# 140715_AriloTX_REV3_0_0_433MHZ_td.net
KiCad netlist of a schematic drawn in EAGLE
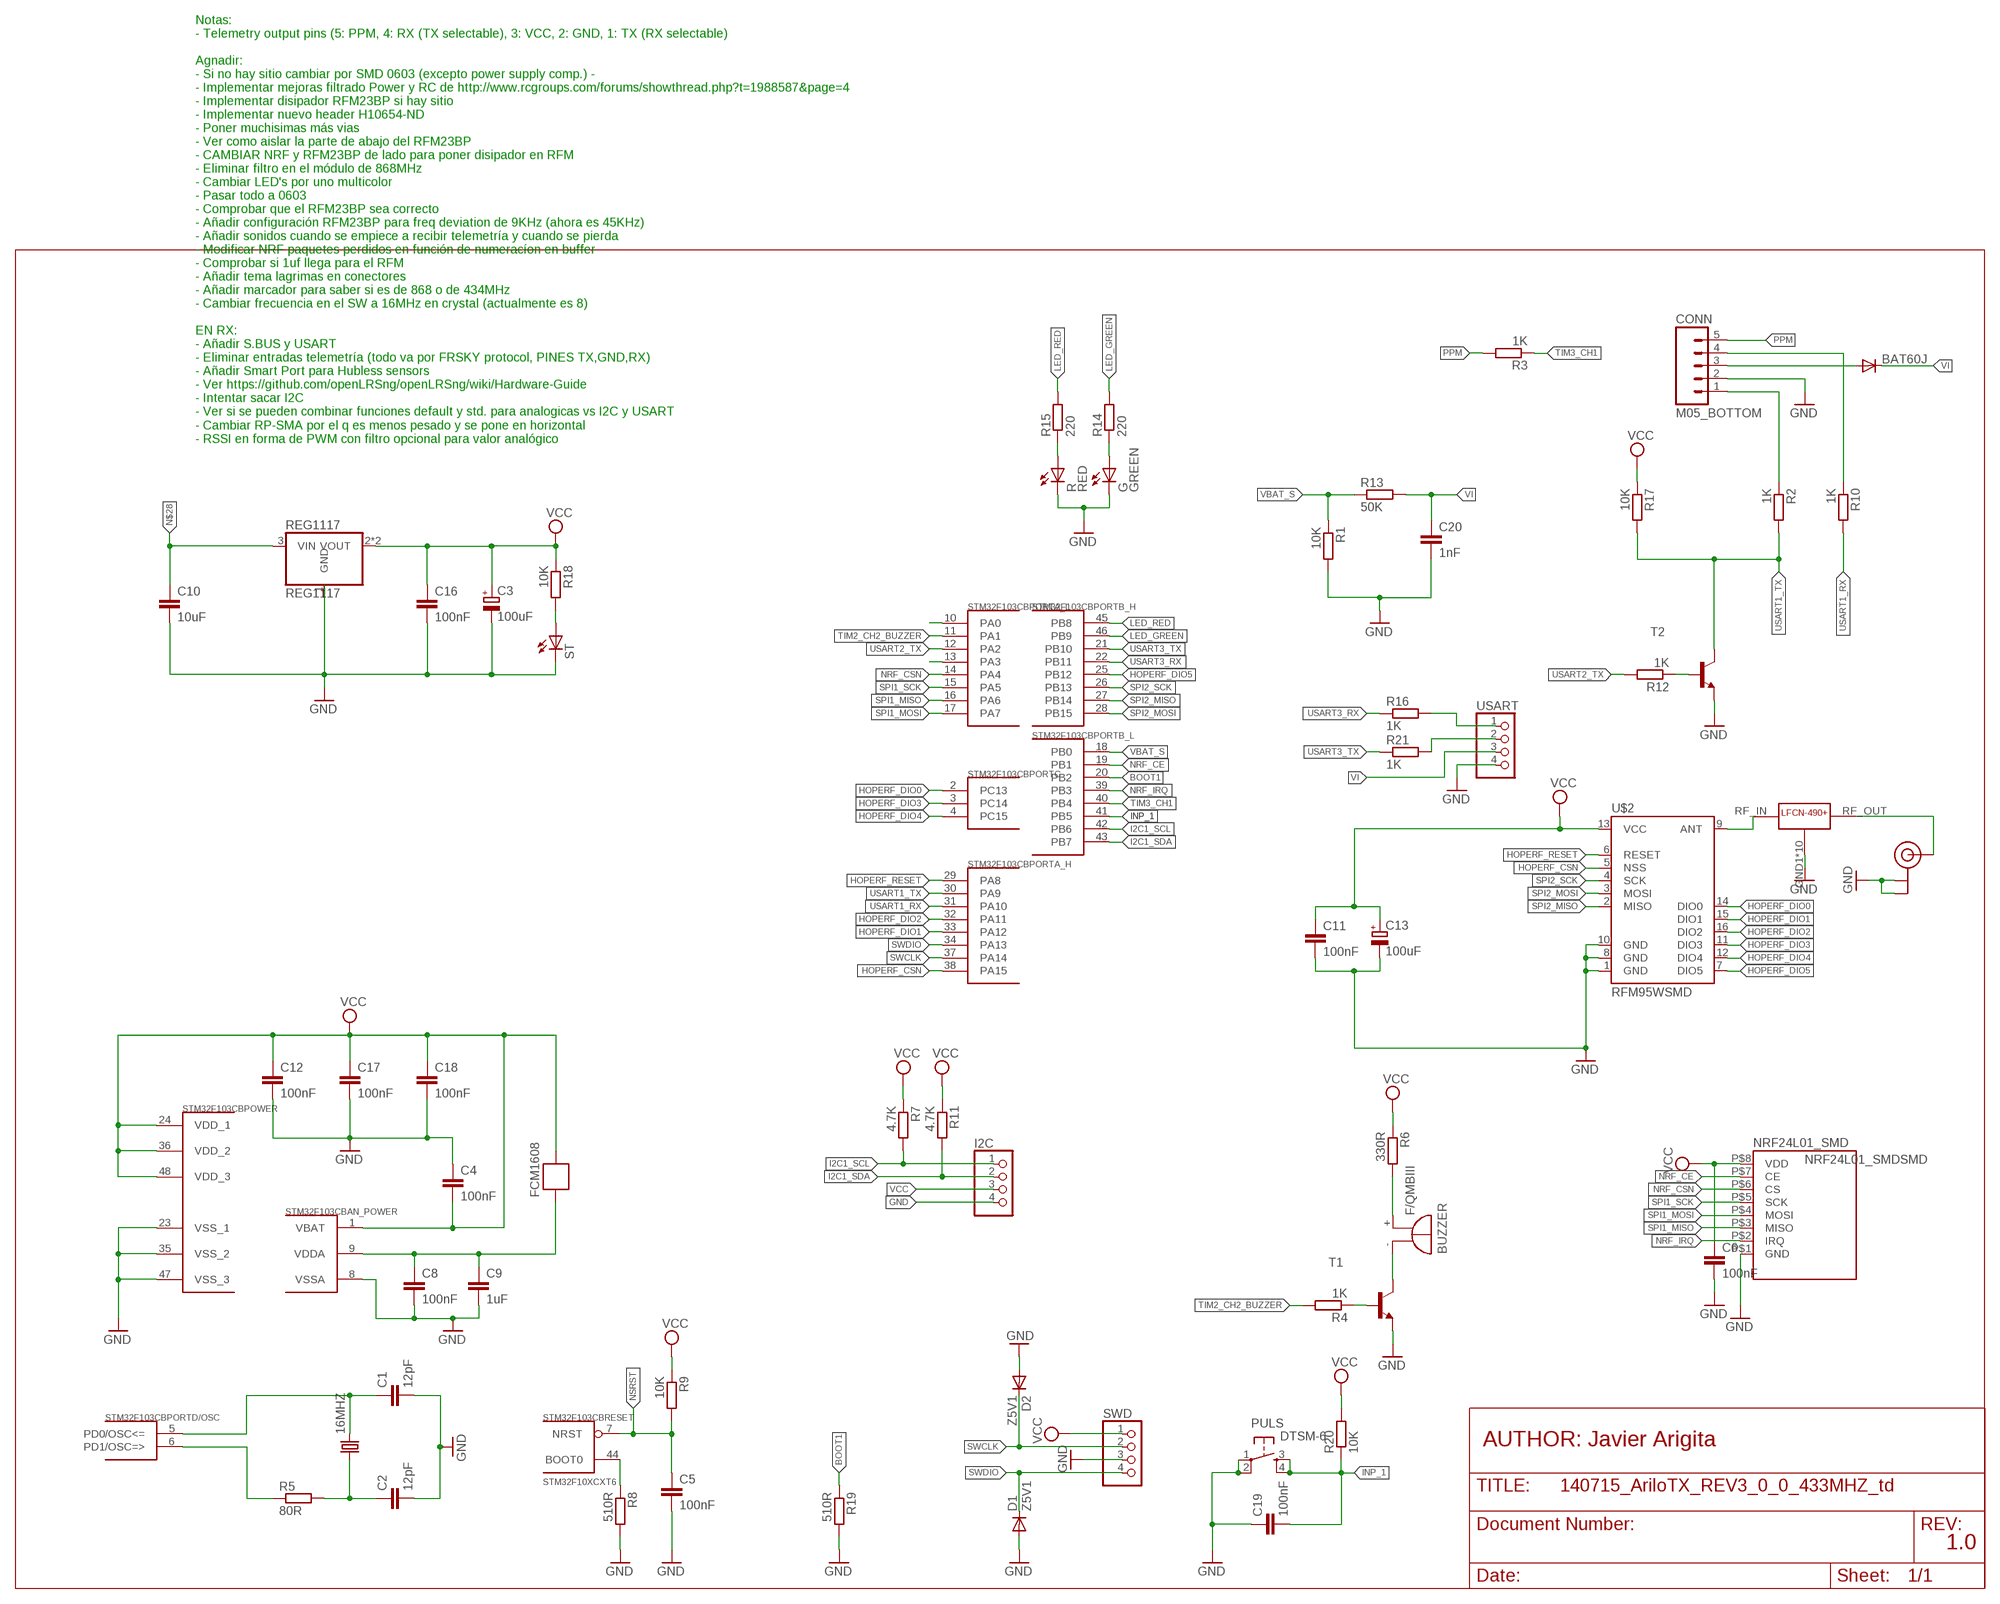
[diagram p0: schematic, sheet 1]

(export (version "E")
  (design (tool "Eeschema 10.0.6"))
  (components
    (comp (ref "16MHZ")
      (value "CRYSTAL5X3")
      (footprint "eagle-import:CRYSTAL-SMD-5X3")
      (libsource (lib "eagle-import") (part "CRYSTAL5X3"))
    )
    (comp (ref "BAT60J")
      (value "DIODE-SOD323-R")
      (footprint "eagle-import:SOD323-R")
      (libsource (lib "eagle-import") (part "DIODE-SOD323-R"))
    )
    (comp (ref "BUZZER")
      (value "F/QMBIII")
      (footprint "eagle-import:F_QMBIII")
      (libsource (lib "eagle-import") (part "F/QMBIII"))
    )
    (comp (ref "C1")
      (value "12pF")
      (footprint "eagle-import:C0603")
      (libsource (lib "eagle-import") (part "C-EUC0603"))
    )
    (comp (ref "C2")
      (value "12pF")
      (footprint "eagle-import:C0603")
      (libsource (lib "eagle-import") (part "C-EUC0603"))
    )
    (comp (ref "C3")
      (value "100uF")
      (footprint "eagle-import:SMC_B")
      (libsource (lib "eagle-import") (part "CPOL-EUSMCB"))
    )
    (comp (ref "C4")
      (value "100nF")
      (footprint "eagle-import:C0603")
      (libsource (lib "eagle-import") (part "C-EUC0603"))
    )
    (comp (ref "C5")
      (value "100nF")
      (footprint "eagle-import:C0603")
      (libsource (lib "eagle-import") (part "C-EUC0603"))
    )
    (comp (ref "C6")
      (value "100nF")
      (footprint "eagle-import:C0603")
      (libsource (lib "eagle-import") (part "C-EUC0603"))
    )
    (comp (ref "C8")
      (value "100nF")
      (footprint "eagle-import:C0603")
      (libsource (lib "eagle-import") (part "C-EUC0603"))
    )
    (comp (ref "C9")
      (value "1uF")
      (footprint "eagle-import:C0603")
      (libsource (lib "eagle-import") (part "C-EUC0603"))
    )
    (comp (ref "C10")
      (value "10uF")
      (footprint "eagle-import:C3216")
      (libsource (lib "eagle-import") (part "resistor_C-EUC3216"))
    )
    (comp (ref "C11")
      (value "100nF")
      (footprint "eagle-import:C0603")
      (libsource (lib "eagle-import") (part "C-EUC0603"))
    )
    (comp (ref "C12")
      (value "100nF")
      (footprint "eagle-import:C0603")
      (libsource (lib "eagle-import") (part "C-EUC0603"))
    )
    (comp (ref "C13")
      (value "100uF")
      (footprint "eagle-import:SMC_B")
      (libsource (lib "eagle-import") (part "CPOL-EUSMCB"))
    )
    (comp (ref "C16")
      (value "100nF")
      (footprint "eagle-import:C0603")
      (libsource (lib "eagle-import") (part "C-EUC0603"))
    )
    (comp (ref "C17")
      (value "100nF")
      (footprint "eagle-import:C0603")
      (libsource (lib "eagle-import") (part "C-EUC0603"))
    )
    (comp (ref "C18")
      (value "100nF")
      (footprint "eagle-import:C0603")
      (libsource (lib "eagle-import") (part "C-EUC0603"))
    )
    (comp (ref "C19")
      (value "100nF")
      (footprint "eagle-import:C0603")
      (libsource (lib "eagle-import") (part "C-EUC0603"))
    )
    (comp (ref "C20")
      (value "1nF")
      (footprint "eagle-import:C0603")
      (libsource (lib "eagle-import") (part "C-EUC0603"))
    )
    (comp (ref "CONN")
      (value "M05_BOTTOM")
      (footprint "eagle-import:M05_BOTTOM")
      (libsource (lib "eagle-import") (part "M05_BOTTOM"))
    )
    (comp (ref "D1")
      (value "Z5V1")
      (footprint "eagle-import:SOD323-R")
      (libsource (lib "eagle-import") (part "DIODE-SOD323-R"))
    )
    (comp (ref "D2")
      (value "Z5V1")
      (footprint "eagle-import:SOD323-R")
      (libsource (lib "eagle-import") (part "DIODE-SOD323-R"))
    )
    (comp (ref "FCM1608")
      (value "FERRITE-BEAD")
      (footprint "eagle-import:R0603")
      (libsource (lib "eagle-import") (part "FERRITE-BEAD"))
    )
    (comp (ref "G")
      (value "GREEN")
      (footprint "eagle-import:CHIP-LED0603")
      (libsource (lib "eagle-import") (part "LEDCHIP-LED0603"))
    )
    (comp (ref "I2C")
      (value "PINHD-1X4")
      (footprint "eagle-import:1X04")
      (libsource (lib "eagle-import") (part "PINHD-1X4"))
    )
    (comp (ref "LFCN490+")
      (value "LFCN490+")
      (footprint "eagle-import:LFCN490+")
      (libsource (lib "eagle-import") (part "LFCN490+"))
    )
    (comp (ref "NRF24L01_SMD")
      (value "NRF24L01_SMDSMD")
      (footprint "eagle-import:NRF24L01_SMD")
      (libsource (lib "eagle-import") (part "NRF24L01_SMDSMD"))
    )
    (comp (ref "PULS")
      (value "DTSM-6")
      (footprint "eagle-import:DTSM-6")
      (libsource (lib "eagle-import") (part "DTSM-6"))
    )
    (comp (ref "R")
      (value "RED")
      (footprint "eagle-import:CHIP-LED0603")
      (libsource (lib "eagle-import") (part "LEDCHIP-LED0603"))
    )
    (comp (ref "R1")
      (value "10K")
      (footprint "eagle-import:R0603")
      (libsource (lib "eagle-import") (part "R-EU_R0603"))
    )
    (comp (ref "R2")
      (value "1K")
      (footprint "eagle-import:R0603")
      (libsource (lib "eagle-import") (part "R-EU_R0603"))
    )
    (comp (ref "R3")
      (value "1K")
      (footprint "eagle-import:R0603")
      (libsource (lib "eagle-import") (part "R-EU_R0603"))
    )
    (comp (ref "R4")
      (value "1K")
      (footprint "eagle-import:R0603")
      (libsource (lib "eagle-import") (part "R-EU_R0603"))
    )
    (comp (ref "R5")
      (value "80R")
      (footprint "eagle-import:R0603")
      (libsource (lib "eagle-import") (part "R-EU_R0603"))
    )
    (comp (ref "R6")
      (value "330R")
      (footprint "eagle-import:R0603")
      (libsource (lib "eagle-import") (part "R-EU_R0603"))
    )
    (comp (ref "R7")
      (value "4.7K")
      (footprint "eagle-import:R0603")
      (libsource (lib "eagle-import") (part "R-EU_R0603"))
    )
    (comp (ref "R8")
      (value "510R")
      (footprint "eagle-import:R0603")
      (libsource (lib "eagle-import") (part "R-EU_R0603"))
    )
    (comp (ref "R9")
      (value "10K")
      (footprint "eagle-import:R0603")
      (libsource (lib "eagle-import") (part "R-EU_R0603"))
    )
    (comp (ref "R10")
      (value "1K")
      (footprint "eagle-import:R0603")
      (libsource (lib "eagle-import") (part "R-EU_R0603"))
    )
    (comp (ref "R11")
      (value "4.7K")
      (footprint "eagle-import:R0603")
      (libsource (lib "eagle-import") (part "R-EU_R0603"))
    )
    (comp (ref "R12")
      (value "1K")
      (footprint "eagle-import:R0603")
      (libsource (lib "eagle-import") (part "R-EU_R0603"))
    )
    (comp (ref "R13")
      (value "50K")
      (footprint "eagle-import:R0603")
      (libsource (lib "eagle-import") (part "R-EU_R0603"))
    )
    (comp (ref "R14")
      (value "220")
      (footprint "eagle-import:R0603")
      (libsource (lib "eagle-import") (part "R-EU_R0603"))
    )
    (comp (ref "R15")
      (value "220")
      (footprint "eagle-import:R0603")
      (libsource (lib "eagle-import") (part "R-EU_R0603"))
    )
    (comp (ref "R16")
      (value "1K")
      (footprint "eagle-import:R0603")
      (libsource (lib "eagle-import") (part "R-EU_R0603"))
    )
    (comp (ref "R17")
      (value "10K")
      (footprint "eagle-import:R0603")
      (libsource (lib "eagle-import") (part "R-EU_R0603"))
    )
    (comp (ref "R18")
      (value "10K")
      (footprint "eagle-import:R0603")
      (libsource (lib "eagle-import") (part "R-EU_R0603"))
    )
    (comp (ref "R19")
      (value "510R")
      (footprint "eagle-import:R0603")
      (libsource (lib "eagle-import") (part "R-EU_R0603"))
    )
    (comp (ref "R20")
      (value "10K")
      (footprint "eagle-import:R0603")
      (libsource (lib "eagle-import") (part "R-EU_R0603"))
    )
    (comp (ref "R21")
      (value "1K")
      (footprint "eagle-import:R0603")
      (libsource (lib "eagle-import") (part "R-EU_R0603"))
    )
    (comp (ref "REG1117")
      (value "REG1117")
      (footprint "eagle-import:SOT223")
      (libsource (lib "eagle-import") (part "REG1117"))
    )
    (comp (ref "ST")
      (value "LEDCHIP-LED0603")
      (footprint "eagle-import:CHIP-LED0603")
      (libsource (lib "eagle-import") (part "LEDCHIP-LED0603"))
    )
    (comp (ref "STM32F103CB")
      (value "STM32F10XCXT6")
      (footprint "eagle-import:TQFP48")
      (libsource (lib "eagle-import") (part "STM32F10XCXT6"))
    )
    (comp (ref "SWD")
      (value "PINHD-1X4")
      (footprint "eagle-import:1X04")
      (libsource (lib "eagle-import") (part "PINHD-1X4"))
    )
    (comp (ref "T1")
      (value "BC848-NPN-SOT23-BEC")
      (footprint "eagle-import:SOT23-BEC")
      (libsource (lib "eagle-import") (part "-NPN-SOT23-BECBC848"))
    )
    (comp (ref "T2")
      (value "BC848-NPN-SOT23-BEC")
      (footprint "eagle-import:SOT23-BEC")
      (libsource (lib "eagle-import") (part "-NPN-SOT23-BECBC848"))
    )
    (comp (ref "U$2")
      (value "RFM95WSMD")
      (footprint "eagle-import:MISIEK_RFM95W_SMD")
      (libsource (lib "eagle-import") (part "MISIEK_RFM95WSMD"))
    )
    (comp (ref "U.FL")
      (value "U.FL")
      (footprint "eagle-import:U.FL")
      (libsource (lib "eagle-import") (part "U.FL"))
    )
    (comp (ref "USART")
      (value "PINHD-1X4")
      (footprint "eagle-import:1X04")
      (libsource (lib "eagle-import") (part "PINHD-1X4"))
    )
  )
  (nets
    (net (code "1") (name "BOOT1") (class "Default")
      (node (ref "R19") (pin "1") (pinfunction "1_1") (pintype "passive"))
      (node (ref "STM32F103CB") (pin "20") (pinfunction "PB2_20") (pintype "bidirectional"))
    )
    (net (code "2") (name "GND") (class "Default")
      (node (ref "C1") (pin "2") (pinfunction "2_2") (pintype "passive"))
      (node (ref "C10") (pin "2") (pinfunction "2_2") (pintype "passive"))
      (node (ref "C11") (pin "2") (pinfunction "2_2") (pintype "passive"))
      (node (ref "C12") (pin "2") (pinfunction "2_2") (pintype "passive"))
      (node (ref "C13") (pin "-") (pinfunction "-_-") (pintype "passive"))
      (node (ref "C16") (pin "2") (pinfunction "2_2") (pintype "passive"))
      (node (ref "C17") (pin "2") (pinfunction "2_2") (pintype "passive"))
      (node (ref "C18") (pin "2") (pinfunction "2_2") (pintype "passive"))
      (node (ref "C19") (pin "1") (pinfunction "1_1") (pintype "passive"))
      (node (ref "C2") (pin "2") (pinfunction "2_2") (pintype "passive"))
      (node (ref "C20") (pin "2") (pinfunction "2_2") (pintype "passive"))
      (node (ref "C3") (pin "-") (pinfunction "-_-") (pintype "passive"))
      (node (ref "C4") (pin "1") (pinfunction "1_1") (pintype "passive"))
      (node (ref "C5") (pin "2") (pinfunction "2_2") (pintype "passive"))
      (node (ref "C6") (pin "2") (pinfunction "2_2") (pintype "passive"))
      (node (ref "C8") (pin "2") (pinfunction "2_2") (pintype "passive"))
      (node (ref "C9") (pin "2") (pinfunction "2_2") (pintype "passive"))
      (node (ref "CONN") (pin "2") (pinfunction "2_2") (pintype "passive"))
      (node (ref "D1") (pin "A") (pinfunction "A_A") (pintype "passive"))
      (node (ref "D2") (pin "A") (pinfunction "A_A") (pintype "passive"))
      (node (ref "G") (pin "C") (pinfunction "C_C") (pintype "passive"))
      (node (ref "I2C") (pin "4") (pinfunction "4_4") (pintype "passive"))
      (node (ref "LFCN490+") (pin "GND1") (pinfunction "GND_GND1") (pintype "bidirectional"))
      (node (ref "LFCN490+") (pin "GND10") (pinfunction "GND_GND10") (pintype "bidirectional"))
      (node (ref "LFCN490+") (pin "GND2") (pinfunction "GND_GND2") (pintype "bidirectional"))
      (node (ref "LFCN490+") (pin "GND3") (pinfunction "GND_GND3") (pintype "bidirectional"))
      (node (ref "LFCN490+") (pin "GND4") (pinfunction "GND_GND4") (pintype "bidirectional"))
      (node (ref "LFCN490+") (pin "GND5") (pinfunction "GND_GND5") (pintype "bidirectional"))
      (node (ref "LFCN490+") (pin "GND6") (pinfunction "GND_GND6") (pintype "bidirectional"))
      (node (ref "LFCN490+") (pin "GND7") (pinfunction "GND_GND7") (pintype "bidirectional"))
      (node (ref "LFCN490+") (pin "GND8") (pinfunction "GND_GND8") (pintype "bidirectional"))
      (node (ref "LFCN490+") (pin "GND9") (pinfunction "GND_GND9") (pintype "bidirectional"))
      (node (ref "NRF24L01_SMD") (pin "P$1") (pinfunction "GND_P$1") (pintype "power_in"))
      (node (ref "PULS") (pin "1") (pinfunction "1_1") (pintype "passive"))
      (node (ref "PULS") (pin "2") (pinfunction "2_2") (pintype "passive"))
      (node (ref "R") (pin "C") (pinfunction "C_C") (pintype "passive"))
      (node (ref "R1") (pin "2") (pinfunction "2_2") (pintype "passive"))
      (node (ref "R19") (pin "2") (pinfunction "2_2") (pintype "passive"))
      (node (ref "R8") (pin "2") (pinfunction "2_2") (pintype "passive"))
      (node (ref "REG1117") (pin "1") (pinfunction "GND_1") (pintype "power_in"))
      (node (ref "ST") (pin "C") (pinfunction "C_C") (pintype "passive"))
      (node (ref "STM32F103CB") (pin "23") (pinfunction "VSS_1_23") (pintype "power_in"))
      (node (ref "STM32F103CB") (pin "35") (pinfunction "VSS_2_35") (pintype "power_in"))
      (node (ref "STM32F103CB") (pin "47") (pinfunction "VSS_3_47") (pintype "power_in"))
      (node (ref "STM32F103CB") (pin "8") (pinfunction "VSSA_8") (pintype "power_in"))
      (node (ref "SWD") (pin "3") (pinfunction "3_3") (pintype "passive"))
      (node (ref "T1") (pin "E") (pinfunction "E_E") (pintype "passive"))
      (node (ref "T2") (pin "E") (pinfunction "E_E") (pintype "passive"))
      (node (ref "U$2") (pin "1") (pinfunction "GND_1") (pintype "power_in"))
      (node (ref "U$2") (pin "10") (pinfunction "GND_10") (pintype "power_in"))
      (node (ref "U$2") (pin "8") (pinfunction "GND_8") (pintype "power_in"))
      (node (ref "U.FL") (pin "P$1") (pinfunction "GND_P$1") (pintype "bidirectional"))
      (node (ref "U.FL") (pin "P$2") (pinfunction "GND_P$2") (pintype "bidirectional"))
      (node (ref "USART") (pin "4") (pinfunction "4_4") (pintype "passive"))
    )
    (net (code "3") (name "HOPERF_CSN") (class "Default")
      (node (ref "STM32F103CB") (pin "38") (pinfunction "PA15_38") (pintype "bidirectional"))
      (node (ref "U$2") (pin "5") (pinfunction "NSS_5") (pintype "input"))
    )
    (net (code "4") (name "HOPERF_DIO0") (class "Default")
      (node (ref "STM32F103CB") (pin "2") (pinfunction "PC13_2") (pintype "bidirectional"))
      (node (ref "U$2") (pin "14") (pinfunction "DIO0_14") (pintype "input"))
    )
    (net (code "5") (name "HOPERF_DIO1") (class "Default")
      (node (ref "STM32F103CB") (pin "33") (pinfunction "PA12_33") (pintype "bidirectional"))
      (node (ref "U$2") (pin "15") (pinfunction "DIO1_15") (pintype "input"))
    )
    (net (code "6") (name "HOPERF_DIO2") (class "Default")
      (node (ref "STM32F103CB") (pin "32") (pinfunction "PA11_32") (pintype "bidirectional"))
      (node (ref "U$2") (pin "16") (pinfunction "DIO2_16") (pintype "input"))
    )
    (net (code "7") (name "HOPERF_DIO3") (class "Default")
      (node (ref "STM32F103CB") (pin "3") (pinfunction "PC14_3") (pintype "bidirectional"))
      (node (ref "U$2") (pin "11") (pinfunction "DIO3_11") (pintype "bidirectional"))
    )
    (net (code "8") (name "HOPERF_DIO4") (class "Default")
      (node (ref "STM32F103CB") (pin "4") (pinfunction "PC15_4") (pintype "bidirectional"))
      (node (ref "U$2") (pin "12") (pinfunction "DIO4_12") (pintype "bidirectional"))
    )
    (net (code "9") (name "HOPERF_DIO5") (class "Default")
      (node (ref "STM32F103CB") (pin "25") (pinfunction "PB12_25") (pintype "bidirectional"))
      (node (ref "U$2") (pin "7") (pinfunction "DIO5_7") (pintype "bidirectional"))
    )
    (net (code "10") (name "HOPERF_RESET") (class "Default")
      (node (ref "STM32F103CB") (pin "29") (pinfunction "PA8_29") (pintype "bidirectional"))
      (node (ref "U$2") (pin "6") (pinfunction "RESET_6") (pintype "output"))
    )
    (net (code "11") (name "I2C1_SCL") (class "Default")
      (node (ref "I2C") (pin "1") (pinfunction "1_1") (pintype "passive"))
      (node (ref "R7") (pin "2") (pinfunction "2_2") (pintype "passive"))
      (node (ref "STM32F103CB") (pin "42") (pinfunction "PB6_42") (pintype "bidirectional"))
    )
    (net (code "12") (name "I2C1_SDA") (class "Default")
      (node (ref "I2C") (pin "2") (pinfunction "2_2") (pintype "passive"))
      (node (ref "R11") (pin "2") (pinfunction "2_2") (pintype "passive"))
      (node (ref "STM32F103CB") (pin "43") (pinfunction "PB7_43") (pintype "bidirectional"))
    )
    (net (code "13") (name "INP_1") (class "Default")
      (node (ref "C19") (pin "2") (pinfunction "2_2") (pintype "passive"))
      (node (ref "PULS") (pin "3") (pinfunction "3_3") (pintype "passive"))
      (node (ref "PULS") (pin "4") (pinfunction "4_4") (pintype "passive"))
      (node (ref "R20") (pin "1") (pinfunction "1_1") (pintype "passive"))
      (node (ref "STM32F103CB") (pin "41") (pinfunction "PB5_41") (pintype "bidirectional"))
    )
    (net (code "14") (name "LED_GREEN") (class "Default")
      (node (ref "R14") (pin "2") (pinfunction "2_2") (pintype "passive"))
      (node (ref "STM32F103CB") (pin "46") (pinfunction "PB9_46") (pintype "bidirectional"))
    )
    (net (code "15") (name "LED_RED") (class "Default")
      (node (ref "R15") (pin "2") (pinfunction "2_2") (pintype "passive"))
      (node (ref "STM32F103CB") (pin "45") (pinfunction "PB8_45") (pintype "bidirectional"))
    )
    (net (code "16") (name "N$28") (class "Default")
      (node (ref "C10") (pin "1") (pinfunction "1_1") (pintype "passive"))
      (node (ref "REG1117") (pin "3") (pinfunction "VIN_3") (pintype "input"))
    )
    (net (code "17") (name "NRF_CE") (class "Default")
      (node (ref "NRF24L01_SMD") (pin "P$7") (pinfunction "CE_P$7") (pintype "input"))
      (node (ref "STM32F103CB") (pin "19") (pinfunction "PB1_19") (pintype "bidirectional"))
    )
    (net (code "18") (name "NRF_CSN") (class "Default")
      (node (ref "NRF24L01_SMD") (pin "P$6") (pinfunction "CS_P$6") (pintype "input"))
      (node (ref "STM32F103CB") (pin "14") (pinfunction "PA4_14") (pintype "bidirectional"))
    )
    (net (code "19") (name "NRF_IRQ") (class "Default")
      (node (ref "NRF24L01_SMD") (pin "P$2") (pinfunction "IRQ_P$2") (pintype "output"))
      (node (ref "STM32F103CB") (pin "39") (pinfunction "PB3_39") (pintype "bidirectional"))
    )
    (net (code "20") (name "NSRST") (class "Default")
      (node (ref "C5") (pin "1") (pinfunction "1_1") (pintype "passive"))
      (node (ref "R9") (pin "2") (pinfunction "2_2") (pintype "passive"))
      (node (ref "STM32F103CB") (pin "7") (pinfunction "NRST_7") (pintype "input"))
    )
    (net (code "21") (name "Net-(16MHZ-2)") (class "Default")
      (node (ref "16MHZ") (pin "3") (pinfunction "2_3") (pintype "passive"))
      (node (ref "C1") (pin "1") (pinfunction "1_1") (pintype "passive"))
      (node (ref "STM32F103CB") (pin "5") (pinfunction "PD0/OSC<=_5") (pintype "bidirectional"))
    )
    (net (code "22") (name "Net-(16MHZ-Pad1)") (class "Default")
      (node (ref "16MHZ") (pin "1") (pinfunction "1_1") (pintype "passive"))
      (node (ref "C2") (pin "1") (pinfunction "1_1") (pintype "passive"))
      (node (ref "R5") (pin "2") (pinfunction "2_2") (pintype "passive"))
    )
    (net (code "23") (name "Net-(BAT60J-PadA)") (class "Default")
      (node (ref "BAT60J") (pin "A") (pinfunction "A_A") (pintype "passive"))
      (node (ref "CONN") (pin "3") (pinfunction "3_3") (pintype "passive"))
    )
    (net (code "24") (name "Net-(BUZZER-+)") (class "Default")
      (node (ref "BUZZER") (pin "-") (pinfunction "+_-") (pintype "passive"))
      (node (ref "T1") (pin "C") (pinfunction "C_C") (pintype "passive"))
    )
    (net (code "25") (name "Net-(BUZZER--)") (class "Default")
      (node (ref "BUZZER") (pin "+") (pinfunction "-_+") (pintype "passive"))
      (node (ref "R6") (pin "2") (pinfunction "2_2") (pintype "passive"))
    )
    (net (code "26") (name "Net-(CONN-Pad1)") (class "Default")
      (node (ref "CONN") (pin "1") (pinfunction "1_1") (pintype "passive"))
      (node (ref "R2") (pin "1") (pinfunction "1_1") (pintype "passive"))
    )
    (net (code "27") (name "Net-(CONN-Pad4)") (class "Default")
      (node (ref "CONN") (pin "4") (pinfunction "4_4") (pintype "passive"))
      (node (ref "R10") (pin "1") (pinfunction "1_1") (pintype "passive"))
    )
    (net (code "28") (name "Net-(FCM1608-P$2)") (class "Default")
      (node (ref "C8") (pin "1") (pinfunction "1_1") (pintype "passive"))
      (node (ref "C9") (pin "1") (pinfunction "1_1") (pintype "passive"))
      (node (ref "FCM1608") (pin "2") (pinfunction "P$2_2") (pintype "bidirectional"))
      (node (ref "STM32F103CB") (pin "9") (pinfunction "VDDA_9") (pintype "power_in"))
    )
    (net (code "29") (name "Net-(G-PadA)") (class "Default")
      (node (ref "G") (pin "A") (pinfunction "A_A") (pintype "passive"))
      (node (ref "R14") (pin "1") (pinfunction "1_1") (pintype "passive"))
    )
    (net (code "30") (name "Net-(LFCN490+-RF_INP)") (class "Default")
      (node (ref "LFCN490+") (pin "RF_IN") (pinfunction "RF_INP_RF_IN") (pintype "bidirectional"))
      (node (ref "U$2") (pin "9") (pinfunction "ANT_9") (pintype "bidirectional"))
    )
    (net (code "31") (name "Net-(LFCN490+-RF_OUTP)") (class "Default")
      (node (ref "LFCN490+") (pin "RF_OUT") (pinfunction "RF_OUTP_RF_OUT") (pintype "bidirectional"))
      (node (ref "U.FL") (pin "P$3") (pinfunction "SIGNAL_P$3") (pintype "bidirectional"))
    )
    (net (code "32") (name "Net-(R-PadA)") (class "Default")
      (node (ref "R") (pin "A") (pinfunction "A_A") (pintype "passive"))
      (node (ref "R15") (pin "1") (pinfunction "1_1") (pintype "passive"))
    )
    (net (code "33") (name "Net-(R4-Pad1)") (class "Default")
      (node (ref "R4") (pin "1") (pinfunction "1_1") (pintype "passive"))
      (node (ref "T1") (pin "B") (pinfunction "B_B") (pintype "passive"))
    )
    (net (code "34") (name "Net-(R12-Pad1)") (class "Default")
      (node (ref "R12") (pin "1") (pinfunction "1_1") (pintype "passive"))
      (node (ref "T2") (pin "B") (pinfunction "B_B") (pintype "passive"))
    )
    (net (code "35") (name "Net-(R16-Pad2)") (class "Default")
      (node (ref "R16") (pin "2") (pinfunction "2_2") (pintype "passive"))
      (node (ref "USART") (pin "1") (pinfunction "1_1") (pintype "passive"))
    )
    (net (code "36") (name "Net-(R18-Pad2)") (class "Default")
      (node (ref "R18") (pin "2") (pinfunction "2_2") (pintype "passive"))
      (node (ref "ST") (pin "A") (pinfunction "A_A") (pintype "passive"))
    )
    (net (code "37") (name "Net-(R21-Pad2)") (class "Default")
      (node (ref "R21") (pin "2") (pinfunction "2_2") (pintype "passive"))
      (node (ref "USART") (pin "2") (pinfunction "2_2") (pintype "passive"))
    )
    (net (code "38") (name "Net-(STM32F103CBG-PD1{slash}OSC=>)") (class "Default")
      (node (ref "R5") (pin "1") (pinfunction "1_1") (pintype "passive"))
      (node (ref "STM32F103CB") (pin "6") (pinfunction "PD1/OSC=>_6") (pintype "bidirectional"))
    )
    (net (code "39") (name "Net-(STM32F103CBI-BOOT0)") (class "Default")
      (node (ref "R8") (pin "1") (pinfunction "1_1") (pintype "passive"))
      (node (ref "STM32F103CB") (pin "44") (pinfunction "BOOT0_44") (pintype "input"))
    )
    (net (code "40") (name "PPM") (class "Default")
      (node (ref "CONN") (pin "5") (pinfunction "5_5") (pintype "passive"))
      (node (ref "R3") (pin "2") (pinfunction "2_2") (pintype "passive"))
    )
    (net (code "41") (name "SPI1_MISO") (class "Default")
      (node (ref "NRF24L01_SMD") (pin "P$3") (pinfunction "MISO_P$3") (pintype "output"))
      (node (ref "STM32F103CB") (pin "16") (pinfunction "PA6_16") (pintype "bidirectional"))
    )
    (net (code "42") (name "SPI1_MOSI") (class "Default")
      (node (ref "NRF24L01_SMD") (pin "P$4") (pinfunction "MOSI_P$4") (pintype "input"))
      (node (ref "STM32F103CB") (pin "17") (pinfunction "PA7_17") (pintype "bidirectional"))
    )
    (net (code "43") (name "SPI1_SCK") (class "Default")
      (node (ref "NRF24L01_SMD") (pin "P$5") (pinfunction "SCK_P$5") (pintype "input"))
      (node (ref "STM32F103CB") (pin "15") (pinfunction "PA5_15") (pintype "bidirectional"))
    )
    (net (code "44") (name "SPI2_MISO") (class "Default")
      (node (ref "STM32F103CB") (pin "27") (pinfunction "PB14_27") (pintype "bidirectional"))
      (node (ref "U$2") (pin "2") (pinfunction "MISO_2") (pintype "output"))
    )
    (net (code "45") (name "SPI2_MOSI") (class "Default")
      (node (ref "STM32F103CB") (pin "28") (pinfunction "PB15_28") (pintype "bidirectional"))
      (node (ref "U$2") (pin "3") (pinfunction "MOSI_3") (pintype "input"))
    )
    (net (code "46") (name "SPI2_SCK") (class "Default")
      (node (ref "STM32F103CB") (pin "26") (pinfunction "PB13_26") (pintype "bidirectional"))
      (node (ref "U$2") (pin "4") (pinfunction "SCK_4") (pintype "input"))
    )
    (net (code "47") (name "SWCLK") (class "Default")
      (node (ref "D2") (pin "C") (pinfunction "C_C") (pintype "passive"))
      (node (ref "STM32F103CB") (pin "37") (pinfunction "PA14_37") (pintype "bidirectional"))
      (node (ref "SWD") (pin "2") (pinfunction "2_2") (pintype "passive"))
    )
    (net (code "48") (name "SWDIO") (class "Default")
      (node (ref "D1") (pin "C") (pinfunction "C_C") (pintype "passive"))
      (node (ref "STM32F103CB") (pin "34") (pinfunction "PA13_34") (pintype "bidirectional"))
      (node (ref "SWD") (pin "4") (pinfunction "4_4") (pintype "passive"))
    )
    (net (code "49") (name "TIM2_CH2_BUZZER") (class "Default")
      (node (ref "R4") (pin "2") (pinfunction "2_2") (pintype "passive"))
      (node (ref "STM32F103CB") (pin "11") (pinfunction "PA1_11") (pintype "bidirectional"))
    )
    (net (code "50") (name "TIM3_CH1") (class "Default")
      (node (ref "R3") (pin "1") (pinfunction "1_1") (pintype "passive"))
      (node (ref "STM32F103CB") (pin "40") (pinfunction "PB4_40") (pintype "bidirectional"))
    )
    (net (code "51") (name "USART1_RX") (class "Default")
      (node (ref "R10") (pin "2") (pinfunction "2_2") (pintype "passive"))
      (node (ref "STM32F103CB") (pin "31") (pinfunction "PA10_31") (pintype "bidirectional"))
    )
    (net (code "52") (name "USART1_TX") (class "Default")
      (node (ref "R17") (pin "2") (pinfunction "2_2") (pintype "passive"))
      (node (ref "R2") (pin "2") (pinfunction "2_2") (pintype "passive"))
      (node (ref "STM32F103CB") (pin "30") (pinfunction "PA9_30") (pintype "bidirectional"))
      (node (ref "T2") (pin "C") (pinfunction "C_C") (pintype "passive"))
    )
    (net (code "53") (name "USART2_TX") (class "Default")
      (node (ref "R12") (pin "2") (pinfunction "2_2") (pintype "passive"))
      (node (ref "STM32F103CB") (pin "12") (pinfunction "PA2_12") (pintype "bidirectional"))
    )
    (net (code "54") (name "USART3_RX") (class "Default")
      (node (ref "R16") (pin "1") (pinfunction "1_1") (pintype "passive"))
      (node (ref "STM32F103CB") (pin "22") (pinfunction "PB11_22") (pintype "bidirectional"))
    )
    (net (code "55") (name "USART3_TX") (class "Default")
      (node (ref "R21") (pin "1") (pinfunction "1_1") (pintype "passive"))
      (node (ref "STM32F103CB") (pin "21") (pinfunction "PB10_21") (pintype "bidirectional"))
    )
    (net (code "56") (name "VBAT_S") (class "Default")
      (node (ref "R1") (pin "1") (pinfunction "1_1") (pintype "passive"))
      (node (ref "R13") (pin "1") (pinfunction "1_1") (pintype "passive"))
      (node (ref "STM32F103CB") (pin "18") (pinfunction "PB0_18") (pintype "bidirectional"))
    )
    (net (code "57") (name "VCC") (class "Default")
      (node (ref "C11") (pin "1") (pinfunction "1_1") (pintype "passive"))
      (node (ref "C12") (pin "1") (pinfunction "1_1") (pintype "passive"))
      (node (ref "C13") (pin "+") (pinfunction "+_+") (pintype "passive"))
      (node (ref "C16") (pin "1") (pinfunction "1_1") (pintype "passive"))
      (node (ref "C17") (pin "1") (pinfunction "1_1") (pintype "passive"))
      (node (ref "C18") (pin "1") (pinfunction "1_1") (pintype "passive"))
      (node (ref "C3") (pin "+") (pinfunction "+_+") (pintype "passive"))
      (node (ref "C4") (pin "2") (pinfunction "2_2") (pintype "passive"))
      (node (ref "C6") (pin "1") (pinfunction "1_1") (pintype "passive"))
      (node (ref "FCM1608") (pin "1") (pinfunction "P$1_1") (pintype "bidirectional"))
      (node (ref "I2C") (pin "3") (pinfunction "3_3") (pintype "passive"))
      (node (ref "NRF24L01_SMD") (pin "P$8") (pinfunction "VDD_P$8") (pintype "bidirectional"))
      (node (ref "R11") (pin "1") (pinfunction "1_1") (pintype "passive"))
      (node (ref "R17") (pin "1") (pinfunction "1_1") (pintype "passive"))
      (node (ref "R18") (pin "1") (pinfunction "1_1") (pintype "passive"))
      (node (ref "R20") (pin "2") (pinfunction "2_2") (pintype "passive"))
      (node (ref "R6") (pin "1") (pinfunction "1_1") (pintype "passive"))
      (node (ref "R7") (pin "1") (pinfunction "1_1") (pintype "passive"))
      (node (ref "R9") (pin "1") (pinfunction "1_1") (pintype "passive"))
      (node (ref "REG1117") (pin "2") (pinfunction "VOUT_2") (pintype "power_in"))
      (node (ref "REG1117") (pin "4") (pinfunction "VOUT_4") (pintype "power_in"))
      (node (ref "STM32F103CB") (pin "1") (pinfunction "VBAT_1") (pintype "power_in"))
      (node (ref "STM32F103CB") (pin "24") (pinfunction "VDD_1_24") (pintype "power_in"))
      (node (ref "STM32F103CB") (pin "36") (pinfunction "VDD_2_36") (pintype "power_in"))
      (node (ref "STM32F103CB") (pin "48") (pinfunction "VDD_3_48") (pintype "power_in"))
      (node (ref "SWD") (pin "1") (pinfunction "1_1") (pintype "passive"))
      (node (ref "U$2") (pin "13") (pinfunction "VCC_13") (pintype "bidirectional"))
    )
    (net (code "58") (name "VI") (class "Default")
      (node (ref "BAT60J") (pin "C") (pinfunction "C_C") (pintype "passive"))
      (node (ref "C20") (pin "1") (pinfunction "1_1") (pintype "passive"))
      (node (ref "R13") (pin "2") (pinfunction "2_2") (pintype "passive"))
      (node (ref "USART") (pin "3") (pinfunction "3_3") (pintype "passive"))
    )
    (net (code "59") (name "unconnected-(STM32F103CBC-PA0-Pad10)") (class "Default")
      (node (ref "STM32F103CB") (pin "10") (pinfunction "PA0_10") (pintype "bidirectional"))
    )
    (net (code "60") (name "unconnected-(STM32F103CBC-PA3-Pad13)") (class "Default")
      (node (ref "STM32F103CB") (pin "13") (pinfunction "PA3_13") (pintype "bidirectional"))
    )
  )
)
